# button.net
KiCad netlist of a schematic drawn in EAGLE
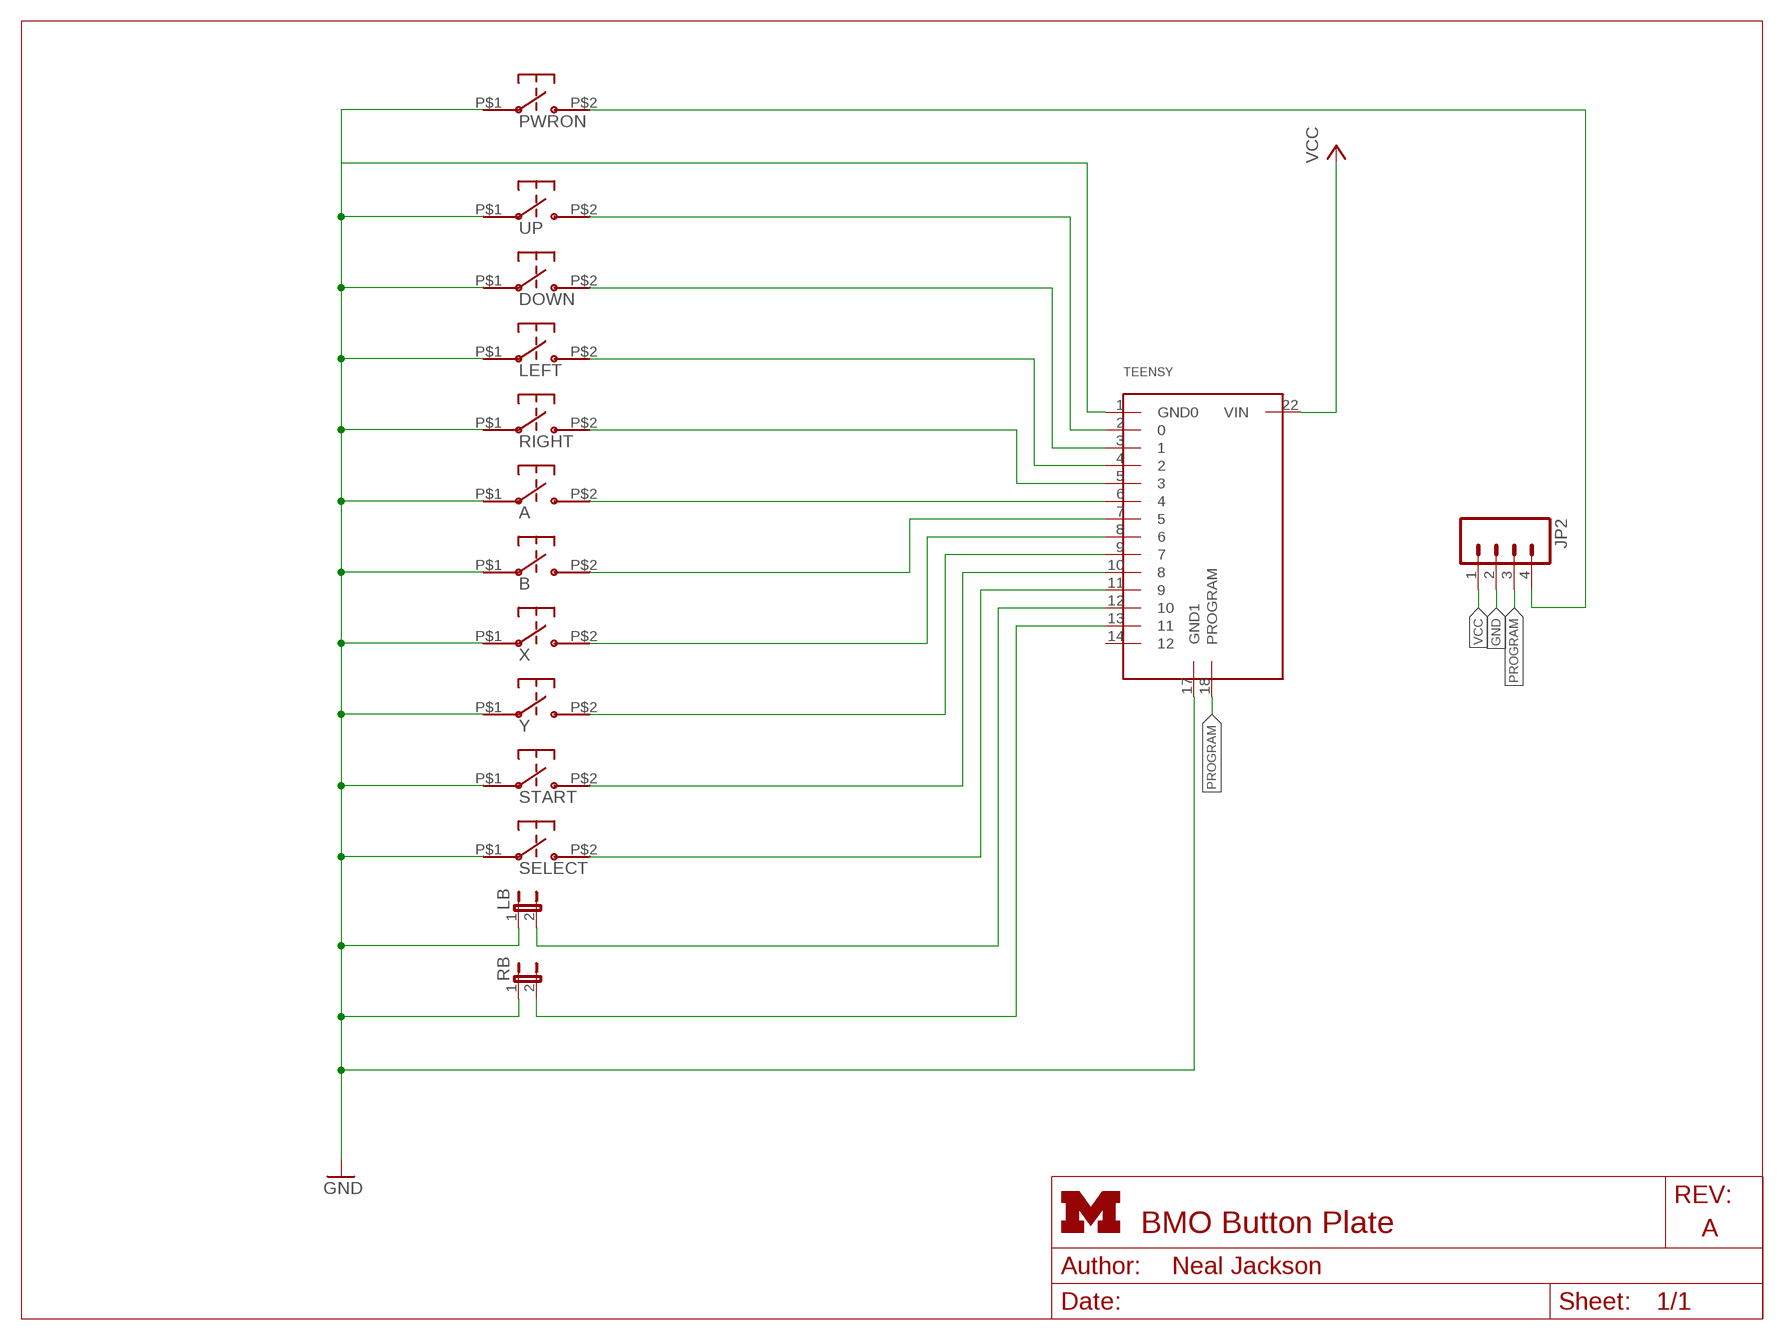
[diagram p0: schematic, sheet 1]

(export (version "E")
  (design (tool "Eeschema 10.0.6"))
  (components
    (comp (ref "A")
      (value "SKPDAMD010")
      (footprint "eagle-import:SKPDAMD010")
      (libsource (lib "eagle-import") (part "SKPDAMD010"))
    )
    (comp (ref "B")
      (value "SKPDAMD010")
      (footprint "eagle-import:SKPDAMD010")
      (libsource (lib "eagle-import") (part "SKPDAMD010"))
    )
    (comp (ref "DOWN")
      (value "SKPDAMD010")
      (footprint "eagle-import:SKPDAMD010")
      (libsource (lib "eagle-import") (part "SKPDAMD010"))
    )
    (comp (ref "JP2")
      (value "M04PTH")
      (footprint "eagle-import:1X04")
      (libsource (lib "eagle-import") (part "M04PTH"))
    )
    (comp (ref "LB")
      (value "JUMPER-2PTH")
      (footprint "eagle-import:1X02")
      (libsource (lib "eagle-import") (part "JUMPER-2PTH"))
    )
    (comp (ref "LEFT")
      (value "SKPDAMD010")
      (footprint "eagle-import:SKPDAMD010")
      (libsource (lib "eagle-import") (part "SKPDAMD010"))
    )
    (comp (ref "PWRON")
      (value "SKPDAMD010")
      (footprint "eagle-import:SKPDAMD010")
      (libsource (lib "eagle-import") (part "SKPDAMD010"))
    )
    (comp (ref "RB")
      (value "JUMPER-2PTH")
      (footprint "eagle-import:1X02")
      (libsource (lib "eagle-import") (part "JUMPER-2PTH"))
    )
    (comp (ref "RIGHT")
      (value "SKPDAMD010")
      (footprint "eagle-import:SKPDAMD010")
      (libsource (lib "eagle-import") (part "SKPDAMD010"))
    )
    (comp (ref "SELECT")
      (value "EVQ11D09K")
      (footprint "eagle-import:EVQ11D09K")
      (libsource (lib "eagle-import") (part "EVQ11D09K"))
    )
    (comp (ref "START")
      (value "EVQ11D09K")
      (footprint "eagle-import:EVQ11D09K")
      (libsource (lib "eagle-import") (part "EVQ11D09K"))
    )
    (comp (ref "TEENSY")
      (value "TEENSY_LC")
      (footprint "eagle-import:TEENSY_LC")
      (libsource (lib "eagle-import") (part "TEENSY_LC"))
    )
    (comp (ref "UP")
      (value "SKPDAMD010")
      (footprint "eagle-import:SKPDAMD010")
      (libsource (lib "eagle-import") (part "SKPDAMD010"))
    )
    (comp (ref "X")
      (value "SKPDAMD010")
      (footprint "eagle-import:SKPDAMD010")
      (libsource (lib "eagle-import") (part "SKPDAMD010"))
    )
    (comp (ref "Y")
      (value "SKPDAMD010")
      (footprint "eagle-import:SKPDAMD010")
      (libsource (lib "eagle-import") (part "SKPDAMD010"))
    )
  )
  (nets
    (net (code "1") (name "GND") (class "Default")
      (node (ref "A") (pin "P$1") (pinfunction "P$1_P$1") (pintype "passive"))
      (node (ref "B") (pin "P$1") (pinfunction "P$1_P$1") (pintype "passive"))
      (node (ref "DOWN") (pin "P$1") (pinfunction "P$1_P$1") (pintype "passive"))
      (node (ref "JP2") (pin "2") (pinfunction "2_2") (pintype "passive"))
      (node (ref "LB") (pin "1") (pinfunction "1_1") (pintype "passive"))
      (node (ref "LEFT") (pin "P$1") (pinfunction "P$1_P$1") (pintype "passive"))
      (node (ref "PWRON") (pin "P$1") (pinfunction "P$1_P$1") (pintype "passive"))
      (node (ref "RB") (pin "1") (pinfunction "1_1") (pintype "passive"))
      (node (ref "RIGHT") (pin "P$1") (pinfunction "P$1_P$1") (pintype "passive"))
      (node (ref "SELECT") (pin "P$1") (pinfunction "P$1_P$1") (pintype "passive"))
      (node (ref "START") (pin "P$1") (pinfunction "P$1_P$1") (pintype "passive"))
      (node (ref "TEENSY") (pin "1") (pinfunction "GND0_1") (pintype "bidirectional"))
      (node (ref "TEENSY") (pin "17") (pinfunction "GND1_17") (pintype "bidirectional"))
      (node (ref "UP") (pin "P$1") (pinfunction "P$1_P$1") (pintype "passive"))
      (node (ref "X") (pin "P$1") (pinfunction "P$1_P$1") (pintype "passive"))
      (node (ref "Y") (pin "P$1") (pinfunction "P$1_P$1") (pintype "passive"))
    )
    (net (code "2") (name "Net-(JP2-Pad4)") (class "Default")
      (node (ref "JP2") (pin "4") (pinfunction "4_4") (pintype "passive"))
      (node (ref "PWRON") (pin "P$2") (pinfunction "P$2_P$2") (pintype "passive"))
    )
    (net (code "3") (name "Net-(TEENSY-0)") (class "Default")
      (node (ref "TEENSY") (pin "2") (pinfunction "0_2") (pintype "bidirectional"))
      (node (ref "UP") (pin "P$2") (pinfunction "P$2_P$2") (pintype "passive"))
    )
    (net (code "4") (name "Net-(TEENSY-1)") (class "Default")
      (node (ref "DOWN") (pin "P$2") (pinfunction "P$2_P$2") (pintype "passive"))
      (node (ref "TEENSY") (pin "3") (pinfunction "1_3") (pintype "bidirectional"))
    )
    (net (code "5") (name "Net-(TEENSY-2)") (class "Default")
      (node (ref "LEFT") (pin "P$2") (pinfunction "P$2_P$2") (pintype "passive"))
      (node (ref "TEENSY") (pin "4") (pinfunction "2_4") (pintype "bidirectional"))
    )
    (net (code "6") (name "Net-(TEENSY-3)") (class "Default")
      (node (ref "RIGHT") (pin "P$2") (pinfunction "P$2_P$2") (pintype "passive"))
      (node (ref "TEENSY") (pin "5") (pinfunction "3_5") (pintype "bidirectional"))
    )
    (net (code "7") (name "Net-(TEENSY-4)") (class "Default")
      (node (ref "A") (pin "P$2") (pinfunction "P$2_P$2") (pintype "passive"))
      (node (ref "TEENSY") (pin "6") (pinfunction "4_6") (pintype "bidirectional"))
    )
    (net (code "8") (name "Net-(TEENSY-5)") (class "Default")
      (node (ref "B") (pin "P$2") (pinfunction "P$2_P$2") (pintype "passive"))
      (node (ref "TEENSY") (pin "7") (pinfunction "5_7") (pintype "bidirectional"))
    )
    (net (code "9") (name "Net-(TEENSY-6)") (class "Default")
      (node (ref "TEENSY") (pin "8") (pinfunction "6_8") (pintype "bidirectional"))
      (node (ref "X") (pin "P$2") (pinfunction "P$2_P$2") (pintype "passive"))
    )
    (net (code "10") (name "Net-(TEENSY-7)") (class "Default")
      (node (ref "TEENSY") (pin "9") (pinfunction "7_9") (pintype "bidirectional"))
      (node (ref "Y") (pin "P$2") (pinfunction "P$2_P$2") (pintype "passive"))
    )
    (net (code "11") (name "Net-(TEENSY-8)") (class "Default")
      (node (ref "START") (pin "P$2") (pinfunction "P$2_P$2") (pintype "passive"))
      (node (ref "TEENSY") (pin "10") (pinfunction "8_10") (pintype "bidirectional"))
    )
    (net (code "12") (name "Net-(TEENSY-9)") (class "Default")
      (node (ref "SELECT") (pin "P$2") (pinfunction "P$2_P$2") (pintype "passive"))
      (node (ref "TEENSY") (pin "11") (pinfunction "9_11") (pintype "bidirectional"))
    )
    (net (code "13") (name "Net-(TEENSY-10)") (class "Default")
      (node (ref "LB") (pin "2") (pinfunction "2_2") (pintype "passive"))
      (node (ref "TEENSY") (pin "12") (pinfunction "10_12") (pintype "bidirectional"))
    )
    (net (code "14") (name "Net-(TEENSY-11)") (class "Default")
      (node (ref "RB") (pin "2") (pinfunction "2_2") (pintype "passive"))
      (node (ref "TEENSY") (pin "13") (pinfunction "11_13") (pintype "bidirectional"))
    )
    (net (code "15") (name "PROGRAM") (class "Default")
      (node (ref "JP2") (pin "3") (pinfunction "3_3") (pintype "passive"))
      (node (ref "TEENSY") (pin "18") (pinfunction "PROGRAM_18") (pintype "bidirectional"))
    )
    (net (code "16") (name "VCC") (class "Default")
      (node (ref "JP2") (pin "1") (pinfunction "1_1") (pintype "passive"))
      (node (ref "TEENSY") (pin "22") (pinfunction "VIN_22") (pintype "bidirectional"))
    )
    (net (code "17") (name "unconnected-(TEENSY-12-Pad14)") (class "Default")
      (node (ref "TEENSY") (pin "14") (pinfunction "12_14") (pintype "bidirectional"))
    )
  )
)
